# zetasdr.net
KiCad netlist of a schematic drawn in EAGLE
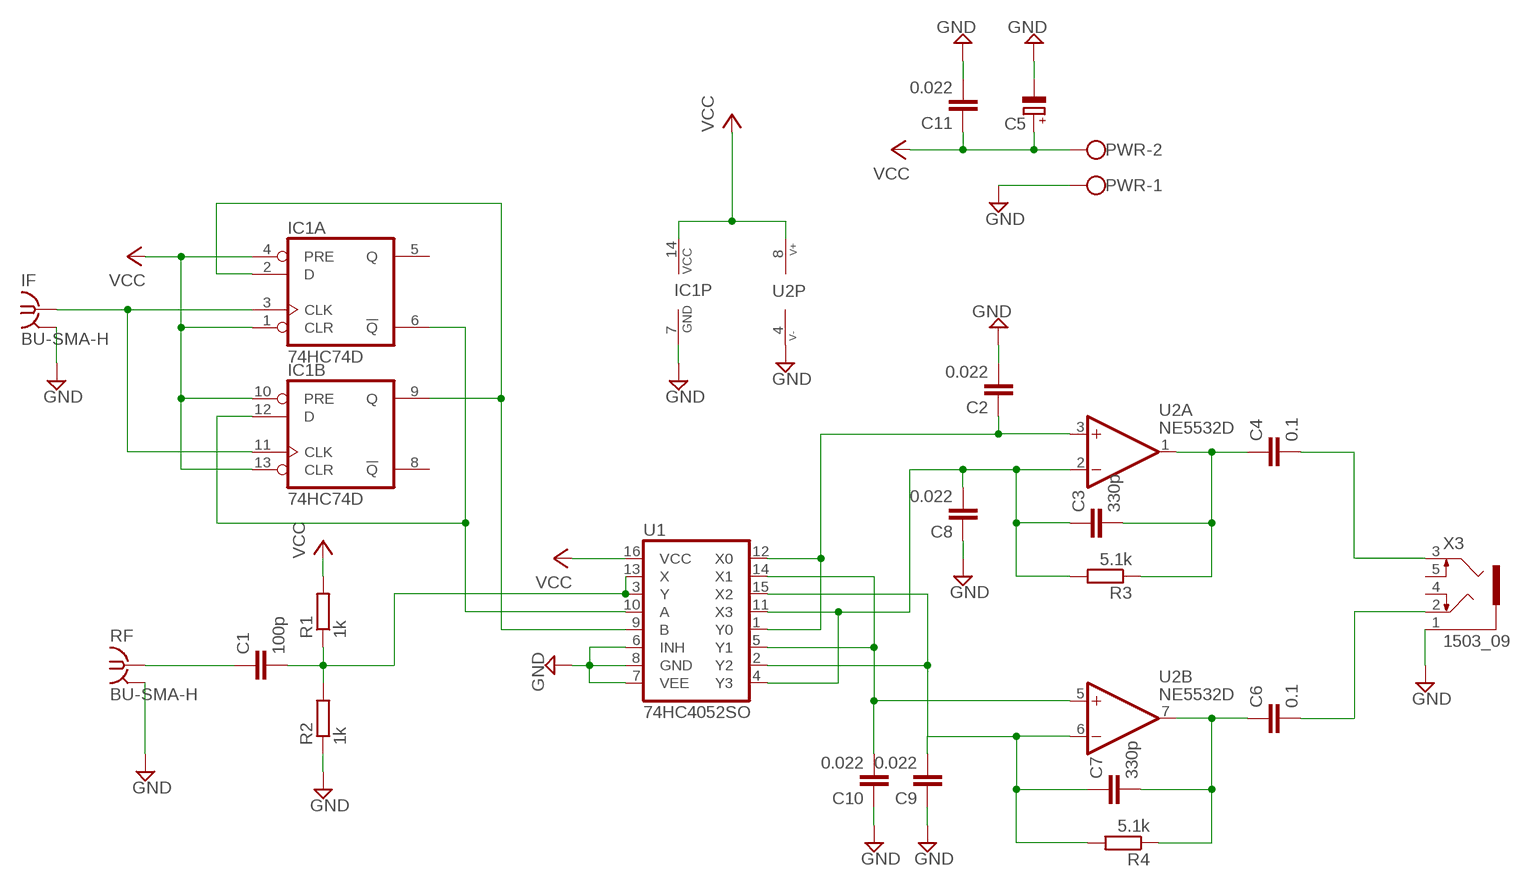
[diagram p0: schematic, sheet 1]

(export (version "E")
  (design (tool "Eeschema 10.0.6"))
  (components
    (comp (ref "C1")
      (value "100p")
      (footprint "eagle-import:C0805")
      (libsource (lib "eagle-import") (part "C-EUC0805"))
    )
    (comp (ref "C2")
      (value "0.022")
      (footprint "eagle-import:C0805")
      (libsource (lib "eagle-import") (part "C-EUC0805"))
    )
    (comp (ref "C3")
      (value "330p")
      (footprint "eagle-import:C0805")
      (libsource (lib "eagle-import") (part "C-EUC0805"))
    )
    (comp (ref "C4")
      (value "0.1")
      (footprint "eagle-import:C050-045X075")
      (libsource (lib "eagle-import") (part "C-EU050-045X075"))
    )
    (comp (ref "C5")
      (value "CPOL-EUE3.5-8")
      (footprint "eagle-import:E3,5-8")
      (libsource (lib "eagle-import") (part "CPOL-EUE3.5-8"))
    )
    (comp (ref "C6")
      (value "0.1")
      (footprint "eagle-import:C050-045X075")
      (libsource (lib "eagle-import") (part "C-EU050-045X075"))
    )
    (comp (ref "C7")
      (value "330p")
      (footprint "eagle-import:C0805")
      (libsource (lib "eagle-import") (part "C-EUC0805"))
    )
    (comp (ref "C8")
      (value "0.022")
      (footprint "eagle-import:C0805")
      (libsource (lib "eagle-import") (part "C-EUC0805"))
    )
    (comp (ref "C9")
      (value "0.022")
      (footprint "eagle-import:C0805")
      (libsource (lib "eagle-import") (part "C-EUC0805"))
    )
    (comp (ref "C10")
      (value "0.022")
      (footprint "eagle-import:C0805")
      (libsource (lib "eagle-import") (part "C-EUC0805"))
    )
    (comp (ref "C11")
      (value "0.022")
      (footprint "eagle-import:C0805")
      (libsource (lib "eagle-import") (part "C-EUC0805"))
    )
    (comp (ref "IC1")
      (value "74HC74D")
      (footprint "eagle-import:SO14")
      (libsource (lib "eagle-import") (part "7474DHC"))
    )
    (comp (ref "IF")
      (value "BU-SMA-H")
      (footprint "eagle-import:BU-SMA-H")
      (libsource (lib "eagle-import") (part "BU-SMA-H"))
    )
    (comp (ref "PWR")
      (value "W237-102")
      (footprint "eagle-import:W237-102")
      (fields (field (name "MPN") "237-102"))
      (libsource (lib "eagle-import") (part "W237-102"))
    )
    (comp (ref "R1")
      (value "1k")
      (footprint "eagle-import:M0805")
      (libsource (lib "eagle-import") (part "R-EU_M0805"))
    )
    (comp (ref "R2")
      (value "1k")
      (footprint "eagle-import:M0805")
      (libsource (lib "eagle-import") (part "R-EU_M0805"))
    )
    (comp (ref "R3")
      (value "5.1k")
      (footprint "eagle-import:R0805")
      (libsource (lib "eagle-import") (part "R-EU_R0805"))
    )
    (comp (ref "R4")
      (value "5.1k")
      (footprint "eagle-import:R0805")
      (libsource (lib "eagle-import") (part "R-EU_R0805"))
    )
    (comp (ref "RF")
      (value "BU-SMA-H")
      (footprint "eagle-import:BU-SMA-H")
      (libsource (lib "eagle-import") (part "BU-SMA-H"))
    )
    (comp (ref "U1")
      (value "74HC4052SO")
      (footprint "eagle-import:SO16")
      (fields (field (name "MF") "Nexperia USA") (field (name "MP") "74HC4052"))
      (libsource (lib "eagle-import") (part "74HC4052SO"))
    )
    (comp (ref "U2")
      (value "NE5532D")
      (footprint "eagle-import:SO08")
      (libsource (lib "eagle-import") (part "NE5532D"))
    )
    (comp (ref "X3")
      (value "1503_09")
      (footprint "eagle-import:1503_09")
      (libsource (lib "eagle-import") (part "1503_09"))
    )
  )
  (nets
    (net (code "1") (name "GND") (class "Default")
      (node (ref "C10") (pin "1") (pinfunction "1_1") (pintype "passive"))
      (node (ref "C11") (pin "2") (pinfunction "2_2") (pintype "passive"))
      (node (ref "C2") (pin "2") (pinfunction "2_2") (pintype "passive"))
      (node (ref "C5") (pin "-") (pinfunction "-_-") (pintype "passive"))
      (node (ref "C8") (pin "1") (pinfunction "1_1") (pintype "passive"))
      (node (ref "C9") (pin "1") (pinfunction "1_1") (pintype "passive"))
      (node (ref "IC1") (pin "7") (pinfunction "GND_7") (pintype "power_in"))
      (node (ref "IF") (pin "2") (pinfunction "2_2") (pintype "passive"))
      (node (ref "IF") (pin "3") (pinfunction "2_3") (pintype "passive"))
      (node (ref "IF") (pin "4") (pinfunction "2_4") (pintype "passive"))
      (node (ref "IF") (pin "5") (pinfunction "2_5") (pintype "passive"))
      (node (ref "PWR") (pin "1") (pinfunction "KL_1") (pintype "passive"))
      (node (ref "R2") (pin "1") (pinfunction "1_1") (pintype "passive"))
      (node (ref "RF") (pin "2") (pinfunction "2_2") (pintype "passive"))
      (node (ref "RF") (pin "3") (pinfunction "2_3") (pintype "passive"))
      (node (ref "RF") (pin "4") (pinfunction "2_4") (pintype "passive"))
      (node (ref "RF") (pin "5") (pinfunction "2_5") (pintype "passive"))
      (node (ref "U1") (pin "6") (pinfunction "INH_6") (pintype "input"))
      (node (ref "U1") (pin "7") (pinfunction "VEE_7") (pintype "power_in"))
      (node (ref "U1") (pin "8") (pinfunction "GND_8") (pintype "power_in"))
      (node (ref "U2") (pin "4") (pinfunction "V-_4") (pintype "power_in"))
      (node (ref "X3") (pin "1") (pinfunction "1_1") (pintype "passive"))
    )
    (net (code "2") (name "Net-(C1-Pad1)") (class "Default")
      (node (ref "C1") (pin "1") (pinfunction "1_1") (pintype "passive"))
      (node (ref "RF") (pin "1") (pinfunction "1_1") (pintype "passive"))
    )
    (net (code "3") (name "Net-(C4-Pad2)") (class "Default")
      (node (ref "C4") (pin "2") (pinfunction "2_2") (pintype "passive"))
      (node (ref "X3") (pin "3") (pinfunction "3_3") (pintype "passive"))
    )
    (net (code "4") (name "Net-(C6-Pad2)") (class "Default")
      (node (ref "C6") (pin "2") (pinfunction "2_2") (pintype "passive"))
      (node (ref "X3") (pin "2") (pinfunction "2_2") (pintype "passive"))
    )
    (net (code "5") (name "Net-(IC1A-CLK)") (class "Default")
      (node (ref "IC1") (pin "11") (pinfunction "CLK_11") (pintype "input"))
      (node (ref "IC1") (pin "3") (pinfunction "CLK_3") (pintype "input"))
      (node (ref "IF") (pin "1") (pinfunction "1_1") (pintype "passive"))
    )
    (net (code "6") (name "Net-(IC1A-D)") (class "Default")
      (node (ref "IC1") (pin "2") (pinfunction "D_2") (pintype "input"))
      (node (ref "IC1") (pin "9") (pinfunction "Q_9") (pintype "output"))
      (node (ref "U1") (pin "9") (pinfunction "B_9") (pintype "input"))
    )
    (net (code "7") (name "Net-(IC1A-~{Q})") (class "Default")
      (node (ref "IC1") (pin "12") (pinfunction "D_12") (pintype "input"))
      (node (ref "IC1") (pin "6") (pinfunction "~{Q}_6") (pintype "output"))
      (node (ref "U1") (pin "10") (pinfunction "A_10") (pintype "input"))
    )
    (net (code "8") (name "Net-(U1-X)") (class "Default")
      (node (ref "C1") (pin "2") (pinfunction "2_2") (pintype "passive"))
      (node (ref "R1") (pin "1") (pinfunction "1_1") (pintype "passive"))
      (node (ref "R2") (pin "2") (pinfunction "2_2") (pintype "passive"))
      (node (ref "U1") (pin "13") (pinfunction "X_13") (pintype "bidirectional"))
      (node (ref "U1") (pin "3") (pinfunction "Y_3") (pintype "bidirectional"))
    )
    (net (code "9") (name "Net-(U1-X0)") (class "Default")
      (node (ref "C2") (pin "1") (pinfunction "1_1") (pintype "passive"))
      (node (ref "U1") (pin "1") (pinfunction "Y0_1") (pintype "bidirectional"))
      (node (ref "U1") (pin "12") (pinfunction "X0_12") (pintype "bidirectional"))
      (node (ref "U2") (pin "3") (pinfunction "+IN_3") (pintype "input"))
    )
    (net (code "10") (name "Net-(U1-X1)") (class "Default")
      (node (ref "C10") (pin "2") (pinfunction "2_2") (pintype "passive"))
      (node (ref "U1") (pin "14") (pinfunction "X1_14") (pintype "bidirectional"))
      (node (ref "U1") (pin "5") (pinfunction "Y1_5") (pintype "bidirectional"))
      (node (ref "U2") (pin "5") (pinfunction "+IN_5") (pintype "input"))
    )
    (net (code "11") (name "Net-(U1-X2)") (class "Default")
      (node (ref "C7") (pin "1") (pinfunction "1_1") (pintype "passive"))
      (node (ref "C9") (pin "2") (pinfunction "2_2") (pintype "passive"))
      (node (ref "R4") (pin "2") (pinfunction "2_2") (pintype "passive"))
      (node (ref "U1") (pin "15") (pinfunction "X2_15") (pintype "bidirectional"))
      (node (ref "U1") (pin "2") (pinfunction "Y2_2") (pintype "bidirectional"))
      (node (ref "U2") (pin "6") (pinfunction "-IN_6") (pintype "input"))
    )
    (net (code "12") (name "Net-(U1-X3)") (class "Default")
      (node (ref "C3") (pin "1") (pinfunction "1_1") (pintype "passive"))
      (node (ref "C8") (pin "2") (pinfunction "2_2") (pintype "passive"))
      (node (ref "R3") (pin "2") (pinfunction "2_2") (pintype "passive"))
      (node (ref "U1") (pin "11") (pinfunction "X3_11") (pintype "bidirectional"))
      (node (ref "U1") (pin "4") (pinfunction "Y3_4") (pintype "bidirectional"))
      (node (ref "U2") (pin "2") (pinfunction "-IN_2") (pintype "input"))
    )
    (net (code "13") (name "Net-(U2A-OUT)") (class "Default")
      (node (ref "C3") (pin "2") (pinfunction "2_2") (pintype "passive"))
      (node (ref "C4") (pin "1") (pinfunction "1_1") (pintype "passive"))
      (node (ref "R3") (pin "1") (pinfunction "1_1") (pintype "passive"))
      (node (ref "U2") (pin "1") (pinfunction "OUT_1") (pintype "output"))
    )
    (net (code "14") (name "Net-(U2B-OUT)") (class "Default")
      (node (ref "C6") (pin "1") (pinfunction "1_1") (pintype "passive"))
      (node (ref "C7") (pin "2") (pinfunction "2_2") (pintype "passive"))
      (node (ref "R4") (pin "1") (pinfunction "1_1") (pintype "passive"))
      (node (ref "U2") (pin "7") (pinfunction "OUT_7") (pintype "output"))
    )
    (net (code "15") (name "VCC") (class "Default")
      (node (ref "C11") (pin "1") (pinfunction "1_1") (pintype "passive"))
      (node (ref "C5") (pin "+") (pinfunction "+_+") (pintype "passive"))
      (node (ref "IC1") (pin "1") (pinfunction "CLR_1") (pintype "input"))
      (node (ref "IC1") (pin "10") (pinfunction "PRE_10") (pintype "input"))
      (node (ref "IC1") (pin "13") (pinfunction "CLR_13") (pintype "input"))
      (node (ref "IC1") (pin "14") (pinfunction "VCC_14") (pintype "power_in"))
      (node (ref "IC1") (pin "4") (pinfunction "PRE_4") (pintype "input"))
      (node (ref "PWR") (pin "2") (pinfunction "KL_2") (pintype "passive"))
      (node (ref "R1") (pin "2") (pinfunction "2_2") (pintype "passive"))
      (node (ref "U1") (pin "16") (pinfunction "VCC_16") (pintype "power_in"))
      (node (ref "U2") (pin "8") (pinfunction "V+_8") (pintype "power_in"))
    )
    (net (code "16") (name "unconnected-(IC1A-Q-Pad5)") (class "Default")
      (node (ref "IC1") (pin "5") (pinfunction "Q_5") (pintype "output"))
    )
    (net (code "17") (name "unconnected-(IC1B-~{Q}-Pad8)") (class "Default")
      (node (ref "IC1") (pin "8") (pinfunction "~{Q}_8") (pintype "output"))
    )
    (net (code "18") (name "unconnected-(X3-Pad4)") (class "Default")
      (node (ref "X3") (pin "4") (pinfunction "4_4") (pintype "passive"))
    )
    (net (code "19") (name "unconnected-(X3-Pad5)") (class "Default")
      (node (ref "X3") (pin "5") (pinfunction "5_5") (pintype "passive"))
    )
  )
)
